# Tiny_PowerSpy.net
KiCad netlist of a schematic drawn in EAGLE
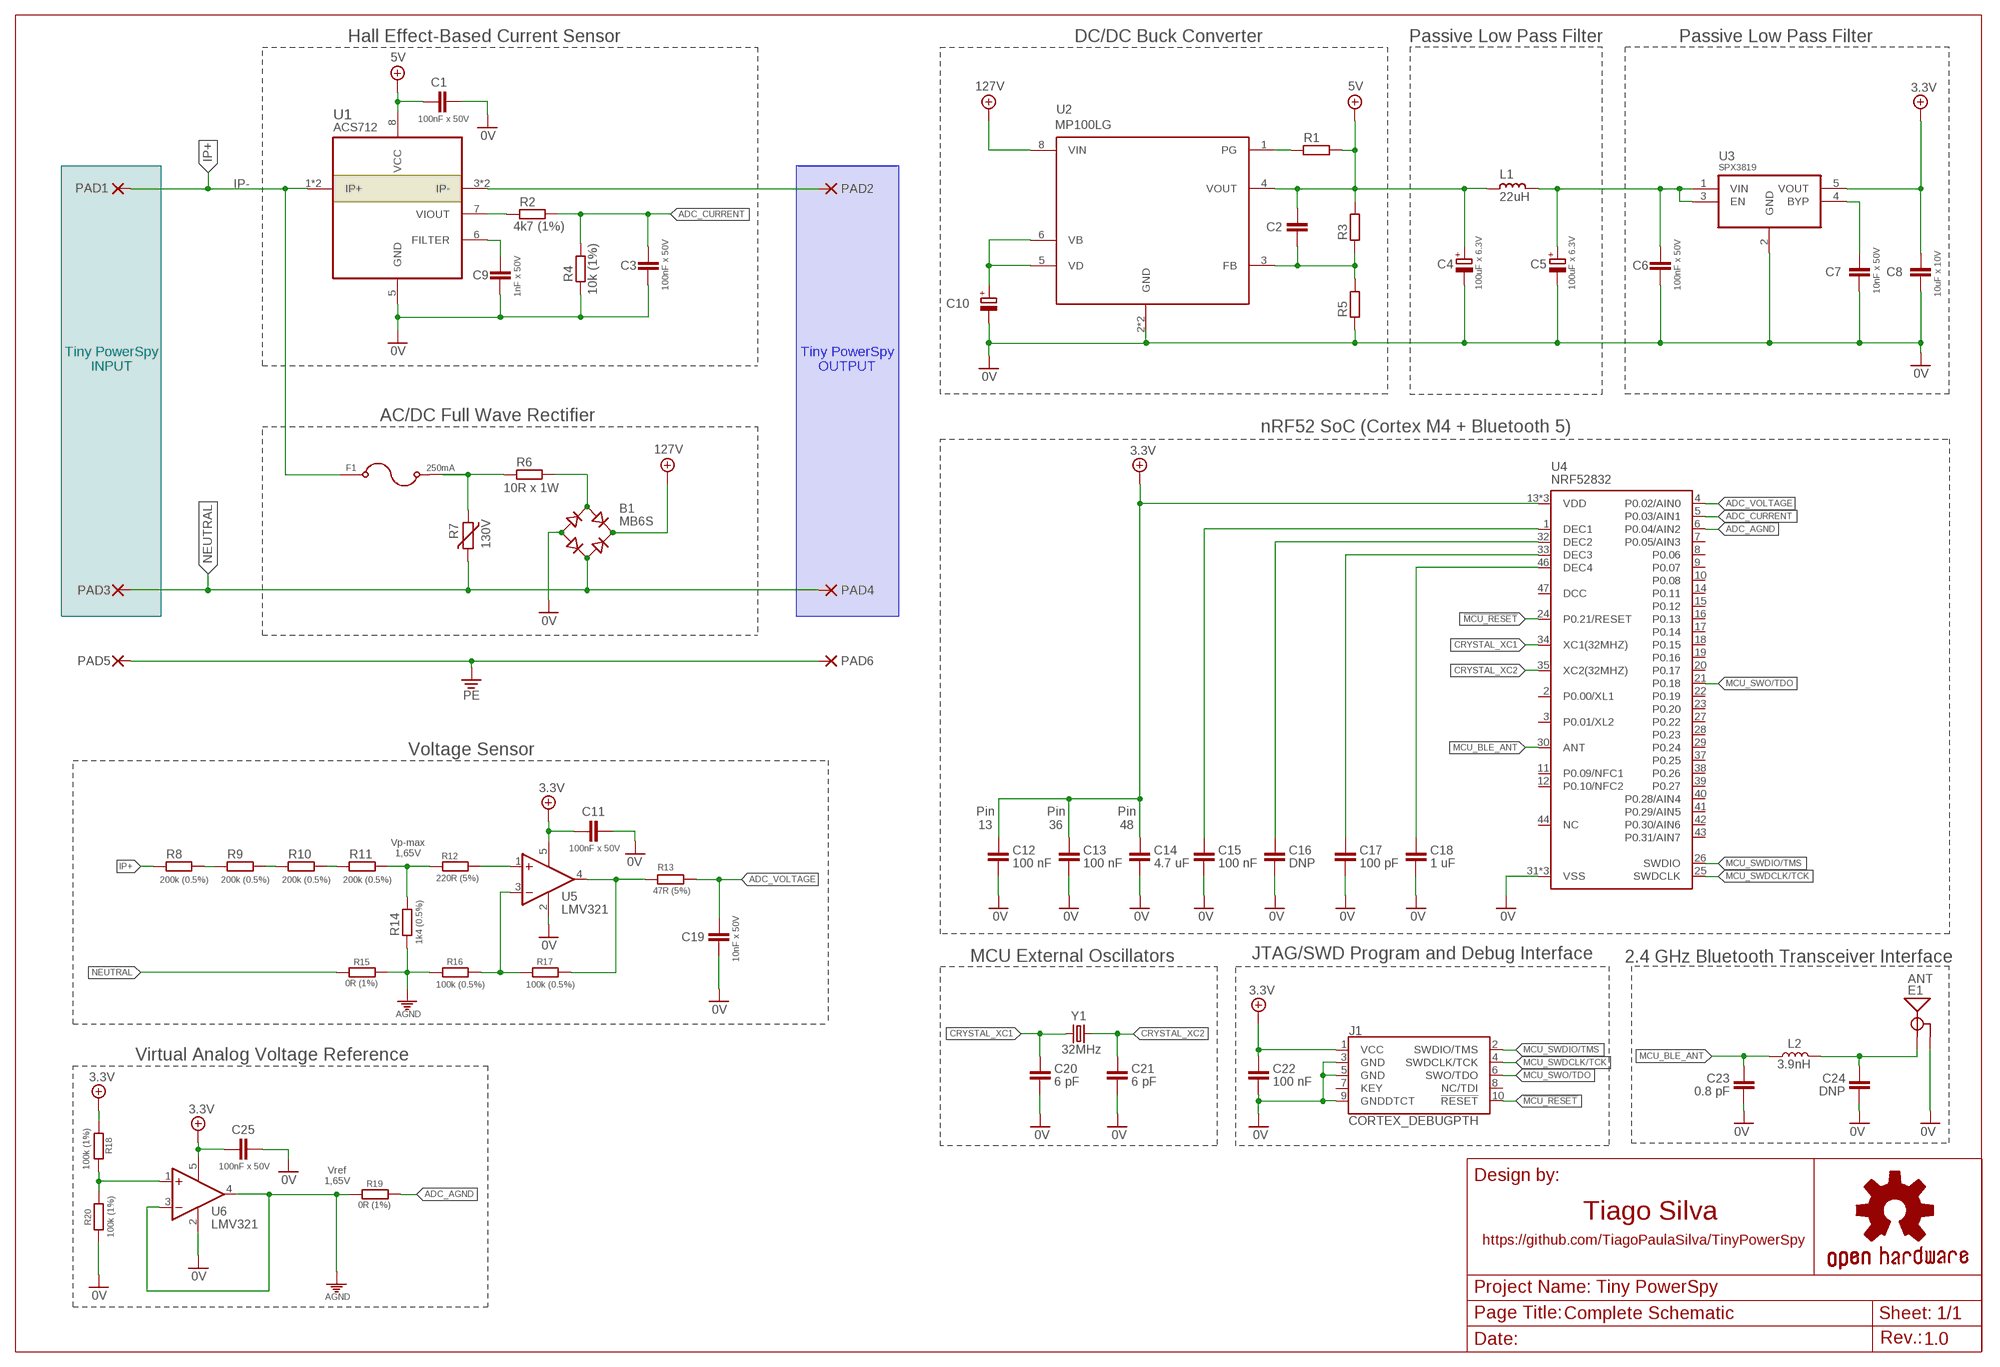
[diagram p0: schematic, sheet 1]

(export (version "E")
  (design (tool "Eeschema 10.0.6"))
  (components
    (comp (ref "B1")
      (value "MB6S")
      (footprint "eagle-import:SOIC-4")
      (libsource (lib "eagle-import") (part "MBS6"))
    )
    (comp (ref "C1")
      (value "100nF x 50V")
      (footprint "eagle-import:C0603")
      (libsource (lib "eagle-import") (part "C-EUC0603"))
    )
    (comp (ref "C2")
      (value "C-EUC0603")
      (footprint "eagle-import:C0603")
      (libsource (lib "eagle-import") (part "C-EUC0603"))
    )
    (comp (ref "C3")
      (value "100nF x 50V")
      (footprint "eagle-import:C0603")
      (libsource (lib "eagle-import") (part "C-EUC0603"))
    )
    (comp (ref "C4")
      (value "100uF x 6.3V")
      (footprint "eagle-import:C1206K")
      (libsource (lib "eagle-import") (part "C-USC1206K"))
    )
    (comp (ref "C5")
      (value "100uF x 6.3V")
      (footprint "eagle-import:C1206K")
      (libsource (lib "eagle-import") (part "C-USC1206K"))
    )
    (comp (ref "C6")
      (value "100nF x 50V")
      (footprint "eagle-import:C0603")
      (libsource (lib "eagle-import") (part "C-EUC0603"))
    )
    (comp (ref "C7")
      (value "10nF x 50V")
      (footprint "eagle-import:C0603")
      (libsource (lib "eagle-import") (part "C-EUC0603"))
    )
    (comp (ref "C8")
      (value "10uF x 10V")
      (footprint "eagle-import:C0603")
      (libsource (lib "eagle-import") (part "C-EUC0603"))
    )
    (comp (ref "C9")
      (value "1nF x 50V")
      (footprint "eagle-import:C0603")
      (libsource (lib "eagle-import") (part "C-EUC0603"))
    )
    (comp (ref "C10")
      (value "CPOL-EUE3.5-8")
      (footprint "eagle-import:E3,5-8")
      (libsource (lib "eagle-import") (part "CPOL-EUE3.5-8"))
    )
    (comp (ref "C11")
      (value "100nF x 50V")
      (footprint "eagle-import:C0603")
      (libsource (lib "eagle-import") (part "C-EUC0603"))
    )
    (comp (ref "C12")
      (value "100 nF")
      (footprint "eagle-import:C0402")
      (libsource (lib "eagle-import") (part "C-EUC0402"))
    )
    (comp (ref "C13")
      (value "100 nF")
      (footprint "eagle-import:C0402")
      (libsource (lib "eagle-import") (part "C-EUC0402"))
    )
    (comp (ref "C14")
      (value "4.7 uF")
      (footprint "eagle-import:C0603")
      (libsource (lib "eagle-import") (part "C-EUC0603"))
    )
    (comp (ref "C15")
      (value "100 nF")
      (footprint "eagle-import:C0402")
      (libsource (lib "eagle-import") (part "C-EUC0402"))
    )
    (comp (ref "C16")
      (value "DNP")
      (footprint "eagle-import:C0402")
      (libsource (lib "eagle-import") (part "C-EUC0402"))
    )
    (comp (ref "C17")
      (value "100 pF")
      (footprint "eagle-import:C0402")
      (libsource (lib "eagle-import") (part "C-EUC0402"))
    )
    (comp (ref "C18")
      (value "1 uF")
      (footprint "eagle-import:C0603")
      (libsource (lib "eagle-import") (part "C-EUC0603"))
    )
    (comp (ref "C19")
      (value "10nF x 50V")
      (footprint "eagle-import:C0603")
      (libsource (lib "eagle-import") (part "C-EUC0603"))
    )
    (comp (ref "C20")
      (value "6 pF")
      (footprint "eagle-import:C0402")
      (libsource (lib "eagle-import") (part "C-EUC0402"))
    )
    (comp (ref "C21")
      (value "6 pF")
      (footprint "eagle-import:C0402")
      (libsource (lib "eagle-import") (part "C-EUC0402"))
    )
    (comp (ref "C22")
      (value "100 nF")
      (footprint "eagle-import:C0603")
      (libsource (lib "eagle-import") (part "C-EUC0603"))
    )
    (comp (ref "C23")
      (value "0.8 pF")
      (footprint "eagle-import:C0603")
      (libsource (lib "eagle-import") (part "C-EUC0603"))
    )
    (comp (ref "C24")
      (value "DNP")
      (footprint "eagle-import:C0603")
      (libsource (lib "eagle-import") (part "C-EUC0603"))
    )
    (comp (ref "C25")
      (value "100nF x 50V")
      (footprint "eagle-import:C0603")
      (libsource (lib "eagle-import") (part "C-EUC0603"))
    )
    (comp (ref "E1")
      (value "ANT")
      (footprint "eagle-import:TRACE_ANTENNA_2.4GHZ_15.2MM")
      (libsource (lib "eagle-import") (part "ANTENNA-GROUNDEDTRACE-15.2MM"))
    )
    (comp (ref "F1")
      (value "250mA")
      (footprint "eagle-import:FUSE_0154004.DR")
      (fields
        (field (name "DIGI-KEY_PART_NUMBER") "F1227CT-ND")
        (field (name "MF") "Littelfuse Inc.")
        (field (name "MP") "0154004.DR")
      )
      (libsource (lib "eagle-import") (part "0154004.DR"))
    )
    (comp (ref "J1")
      (value "CORTEX_DEBUGPTH")
      (footprint "eagle-import:2X5-PTH-1.27MM")
      (libsource (lib "eagle-import") (part "CORTEX_DEBUGPTH"))
    )
    (comp (ref "L1")
      (value "22uH")
      (footprint "eagle-import:L0603")
      (libsource (lib "eagle-import") (part "L_0603"))
    )
    (comp (ref "L2")
      (value "3.9nH")
      (footprint "eagle-import:0402")
      (libsource (lib "eagle-import") (part "INDUCTOR-0402-3.9NH"))
    )
    (comp (ref "PAD1")
      (value "SMD5")
      (footprint "eagle-import:SMD2,54-5,08")
      (libsource (lib "eagle-import") (part "SMD5"))
    )
    (comp (ref "PAD2")
      (value "SMD5")
      (footprint "eagle-import:SMD2,54-5,08")
      (libsource (lib "eagle-import") (part "SMD5"))
    )
    (comp (ref "PAD3")
      (value "SMD2")
      (footprint "eagle-import:SMD1,27-2,54")
      (libsource (lib "eagle-import") (part "SMD2"))
    )
    (comp (ref "PAD4")
      (value "SMD5")
      (footprint "eagle-import:SMD2,54-5,08")
      (libsource (lib "eagle-import") (part "SMD5"))
    )
    (comp (ref "PAD5")
      (value "SMD2")
      (footprint "eagle-import:SMD1,27-2,54")
      (libsource (lib "eagle-import") (part "SMD2"))
    )
    (comp (ref "PAD6")
      (value "SMD5")
      (footprint "eagle-import:SMD2,54-5,08")
      (libsource (lib "eagle-import") (part "SMD5"))
    )
    (comp (ref "R1")
      (value "R-EU_R0603")
      (footprint "eagle-import:R0603")
      (libsource (lib "eagle-import") (part "R-EU_R0603"))
    )
    (comp (ref "R2")
      (value "4k7 (1%)")
      (footprint "eagle-import:R0603")
      (libsource (lib "eagle-import") (part "R-EU_R0603"))
    )
    (comp (ref "R3")
      (value "R-EU_R0603")
      (footprint "eagle-import:R0603")
      (libsource (lib "eagle-import") (part "R-EU_R0603"))
    )
    (comp (ref "R4")
      (value "10k (1%)")
      (footprint "eagle-import:R0603")
      (libsource (lib "eagle-import") (part "R-EU_R0603"))
    )
    (comp (ref "R5")
      (value "R-EU_R0603")
      (footprint "eagle-import:R0603")
      (libsource (lib "eagle-import") (part "R-EU_R0603"))
    )
    (comp (ref "R6")
      (value "10R x 1W")
      (footprint "eagle-import:0207_5V")
      (libsource (lib "eagle-import") (part "resistor pot_R-EU_0207/5V"))
    )
    (comp (ref "R7")
      (value "130V")
      (footprint "eagle-import:S05K11")
      (libsource (lib "eagle-import") (part "VARISTOR"))
    )
    (comp (ref "R8")
      (value "200k (0.5%)")
      (footprint "eagle-import:R0603")
      (libsource (lib "eagle-import") (part "R-EU_R0603"))
    )
    (comp (ref "R9")
      (value "200k (0.5%)")
      (footprint "eagle-import:R0603")
      (libsource (lib "eagle-import") (part "R-EU_R0603"))
    )
    (comp (ref "R10")
      (value "200k (0.5%)")
      (footprint "eagle-import:R0603")
      (libsource (lib "eagle-import") (part "R-EU_R0603"))
    )
    (comp (ref "R11")
      (value "200k (0.5%)")
      (footprint "eagle-import:R0603")
      (libsource (lib "eagle-import") (part "R-EU_R0603"))
    )
    (comp (ref "R12")
      (value "220R (5%)")
      (footprint "eagle-import:R0603")
      (libsource (lib "eagle-import") (part "R-EU_R0603"))
    )
    (comp (ref "R13")
      (value "47R (5%)")
      (footprint "eagle-import:R0603")
      (libsource (lib "eagle-import") (part "R-EU_R0603"))
    )
    (comp (ref "R14")
      (value "1k4 (0.5%)")
      (footprint "eagle-import:R0603")
      (libsource (lib "eagle-import") (part "R-EU_R0603"))
    )
    (comp (ref "R15")
      (value "0R (1%)")
      (footprint "eagle-import:R0603")
      (libsource (lib "eagle-import") (part "R-EU_R0603"))
    )
    (comp (ref "R16")
      (value "100k (0.5%)")
      (footprint "eagle-import:R0603")
      (libsource (lib "eagle-import") (part "R-EU_R0603"))
    )
    (comp (ref "R17")
      (value "100k (0.5%)")
      (footprint "eagle-import:R0603")
      (libsource (lib "eagle-import") (part "R-EU_R0603"))
    )
    (comp (ref "R18")
      (value "100k (1%)")
      (footprint "eagle-import:R0603")
      (libsource (lib "eagle-import") (part "R-EU_R0603"))
    )
    (comp (ref "R19")
      (value "0R (1%)")
      (footprint "eagle-import:R0603")
      (libsource (lib "eagle-import") (part "R-EU_R0603"))
    )
    (comp (ref "R20")
      (value "100k (1%)")
      (footprint "eagle-import:R0603")
      (libsource (lib "eagle-import") (part "R-EU_R0603"))
    )
    (comp (ref "U1")
      (value "ACS712")
      (footprint "eagle-import:SOIC127P600X175-8N")
      (fields (field (name "MF") "Allegro") (field (name "MP") "ACS712ELCTR-20A-T"))
      (libsource (lib "eagle-import") (part "ACS712ELCTR-20A-T"))
    )
    (comp (ref "U2")
      (value "MP100LG")
      (footprint "eagle-import:SOIC8E")
      (libsource (lib "eagle-import") (part "MP100LG"))
    )
    (comp (ref "U3")
      (value "SPX3819")
      (footprint "eagle-import:SOT95P280X145-5N")
      (fields (field (name "MF") "MaxLinear, Inc.") (field (name "MP") "SPX3819M5-L-3-3"))
      (libsource (lib "eagle-import") (part "SPX3819M5-L-3-3"))
    )
    (comp (ref "U4")
      (value "NRF52832")
      (footprint "eagle-import:QFN48-6X6MM")
      (libsource (lib "eagle-import") (part "NRF52832"))
    )
    (comp (ref "U5")
      (value "LMV321")
      (footprint "eagle-import:SOT23-5")
      (libsource (lib "eagle-import") (part "LMV321?M5"))
    )
    (comp (ref "U6")
      (value "LMV321")
      (footprint "eagle-import:SOT23-5")
      (libsource (lib "eagle-import") (part "LMV321?M5"))
    )
    (comp (ref "Y1")
      (value "32MHz")
      (footprint "eagle-import:CRYSTAL-SMD-2.0X1.6MM")
      (libsource (lib "eagle-import") (part "CRYSTAL-32MHZ-SMD-2.0X1.6MM"))
    )
  )
  (nets
    (net (code "1") (name "/IP-") (class "Default")
      (node (ref "PAD2") (pin "1") (pinfunction "P_1") (pintype "passive"))
      (node (ref "U1") (pin "3") (pinfunction "IP-_3") (pintype "input"))
      (node (ref "U1") (pin "4") (pinfunction "IP-_4") (pintype "input"))
    )
    (net (code "2") (name "/~{MCU_RESET}") (class "Default")
      (node (ref "J1") (pin "10") (pinfunction "~{RESET}_10") (pintype "bidirectional"))
      (node (ref "U4") (pin "24") (pinfunction "P0.21/RESET_24") (pintype "bidirectional"))
    )
    (net (code "3") (name "0V") (class "Default")
      (node (ref "B1") (pin "-") (pinfunction "-_-") (pintype "passive"))
      (node (ref "C1") (pin "1") (pinfunction "1_1") (pintype "passive"))
      (node (ref "C10") (pin "-") (pinfunction "-_-") (pintype "passive"))
      (node (ref "C11") (pin "1") (pinfunction "1_1") (pintype "passive"))
      (node (ref "C12") (pin "2") (pinfunction "2_2") (pintype "passive"))
      (node (ref "C13") (pin "2") (pinfunction "2_2") (pintype "passive"))
      (node (ref "C14") (pin "2") (pinfunction "2_2") (pintype "passive"))
      (node (ref "C15") (pin "2") (pinfunction "2_2") (pintype "passive"))
      (node (ref "C16") (pin "2") (pinfunction "2_2") (pintype "passive"))
      (node (ref "C17") (pin "2") (pinfunction "2_2") (pintype "passive"))
      (node (ref "C18") (pin "2") (pinfunction "2_2") (pintype "passive"))
      (node (ref "C19") (pin "2") (pinfunction "2_2") (pintype "passive"))
      (node (ref "C20") (pin "2") (pinfunction "2_2") (pintype "passive"))
      (node (ref "C21") (pin "2") (pinfunction "2_2") (pintype "passive"))
      (node (ref "C22") (pin "2") (pinfunction "2_2") (pintype "passive"))
      (node (ref "C23") (pin "2") (pinfunction "2_2") (pintype "passive"))
      (node (ref "C24") (pin "2") (pinfunction "2_2") (pintype "passive"))
      (node (ref "C25") (pin "2") (pinfunction "2_2") (pintype "passive"))
      (node (ref "C3") (pin "2") (pinfunction "2_2") (pintype "passive"))
      (node (ref "C4") (pin "2") (pinfunction "2_2") (pintype "passive"))
      (node (ref "C5") (pin "2") (pinfunction "2_2") (pintype "passive"))
      (node (ref "C6") (pin "2") (pinfunction "2_2") (pintype "passive"))
      (node (ref "C7") (pin "2") (pinfunction "2_2") (pintype "passive"))
      (node (ref "C8") (pin "2") (pinfunction "2_2") (pintype "passive"))
      (node (ref "C9") (pin "2") (pinfunction "2_2") (pintype "passive"))
      (node (ref "E1") (pin "GND") (pinfunction "GND_GND") (pintype "bidirectional"))
      (node (ref "J1") (pin "3") (pinfunction "GND_3") (pintype "bidirectional"))
      (node (ref "J1") (pin "5") (pinfunction "GND_5") (pintype "bidirectional"))
      (node (ref "J1") (pin "9") (pinfunction "GNDDTCT_9") (pintype "bidirectional"))
      (node (ref "R20") (pin "2") (pinfunction "2_2") (pintype "passive"))
      (node (ref "R4") (pin "2") (pinfunction "2_2") (pintype "passive"))
      (node (ref "R5") (pin "1") (pinfunction "1_1") (pintype "passive"))
      (node (ref "U1") (pin "5") (pinfunction "GND_5") (pintype "power_in"))
      (node (ref "U2") (pin "2") (pinfunction "GND_2") (pintype "bidirectional"))
      (node (ref "U2") (pin "9") (pinfunction "GND_9") (pintype "bidirectional"))
      (node (ref "U3") (pin "2") (pinfunction "GND_2") (pintype "passive"))
      (node (ref "U4") (pin "31") (pinfunction "VSS_31") (pintype "bidirectional"))
      (node (ref "U4") (pin "45") (pinfunction "VSS_45") (pintype "bidirectional"))
      (node (ref "U4") (pin "EP") (pinfunction "VSS_EP") (pintype "bidirectional"))
      (node (ref "U5") (pin "2") (pinfunction "V-_2") (pintype "power_in"))
      (node (ref "U6") (pin "2") (pinfunction "V-_2") (pintype "power_in"))
    )
    (net (code "4") (name "3.3V") (class "Default")
      (node (ref "C11") (pin "2") (pinfunction "2_2") (pintype "passive"))
      (node (ref "C12") (pin "1") (pinfunction "1_1") (pintype "passive"))
      (node (ref "C13") (pin "1") (pinfunction "1_1") (pintype "passive"))
      (node (ref "C14") (pin "1") (pinfunction "1_1") (pintype "passive"))
      (node (ref "C22") (pin "1") (pinfunction "1_1") (pintype "passive"))
      (node (ref "C25") (pin "1") (pinfunction "1_1") (pintype "passive"))
      (node (ref "C8") (pin "1") (pinfunction "1_1") (pintype "passive"))
      (node (ref "J1") (pin "1") (pinfunction "VCC_1") (pintype "bidirectional"))
      (node (ref "R18") (pin "2") (pinfunction "2_2") (pintype "passive"))
      (node (ref "U3") (pin "5") (pinfunction "VOUT_5") (pintype "output"))
      (node (ref "U4") (pin "13") (pinfunction "VDD_13") (pintype "bidirectional"))
      (node (ref "U4") (pin "36") (pinfunction "VDD_36") (pintype "bidirectional"))
      (node (ref "U4") (pin "48") (pinfunction "VDD_48") (pintype "bidirectional"))
      (node (ref "U5") (pin "5") (pinfunction "V+_5") (pintype "power_in"))
      (node (ref "U6") (pin "5") (pinfunction "V+_5") (pintype "power_in"))
    )
    (net (code "5") (name "5V") (class "Default")
      (node (ref "C1") (pin "2") (pinfunction "2_2") (pintype "passive"))
      (node (ref "C2") (pin "1") (pinfunction "1_1") (pintype "passive"))
      (node (ref "C4") (pin "1") (pinfunction "1_1") (pintype "passive"))
      (node (ref "L1") (pin "2") (pinfunction "2_2") (pintype "passive"))
      (node (ref "R1") (pin "2") (pinfunction "2_2") (pintype "passive"))
      (node (ref "R3") (pin "2") (pinfunction "2_2") (pintype "passive"))
      (node (ref "U1") (pin "8") (pinfunction "VCC_8") (pintype "power_in"))
      (node (ref "U2") (pin "4") (pinfunction "VOUT_4") (pintype "bidirectional"))
    )
    (net (code "6") (name "127V") (class "Default")
      (node (ref "B1") (pin "+") (pinfunction "+_+") (pintype "passive"))
      (node (ref "U2") (pin "8") (pinfunction "VIN_8") (pintype "bidirectional"))
    )
    (net (code "7") (name "ADC_AGND") (class "Default")
      (node (ref "R19") (pin "2") (pinfunction "2_2") (pintype "passive"))
      (node (ref "U4") (pin "6") (pinfunction "P0.04/AIN2_6") (pintype "bidirectional"))
    )
    (net (code "8") (name "ADC_CURRENT") (class "Default")
      (node (ref "C3") (pin "1") (pinfunction "1_1") (pintype "passive"))
      (node (ref "R2") (pin "2") (pinfunction "2_2") (pintype "passive"))
      (node (ref "R4") (pin "1") (pinfunction "1_1") (pintype "passive"))
      (node (ref "U4") (pin "5") (pinfunction "P0.03/AIN1_5") (pintype "bidirectional"))
    )
    (net (code "9") (name "ADC_VOLTAGE") (class "Default")
      (node (ref "C19") (pin "1") (pinfunction "1_1") (pintype "passive"))
      (node (ref "R13") (pin "1") (pinfunction "1_1") (pintype "passive"))
      (node (ref "U4") (pin "4") (pinfunction "P0.02/AIN0_4") (pintype "bidirectional"))
    )
    (net (code "10") (name "AGND") (class "Default")
      (node (ref "R14") (pin "2") (pinfunction "2_2") (pintype "passive"))
      (node (ref "R15") (pin "2") (pinfunction "2_2") (pintype "passive"))
      (node (ref "R16") (pin "2") (pinfunction "2_2") (pintype "passive"))
      (node (ref "R19") (pin "1") (pinfunction "1_1") (pintype "passive"))
      (node (ref "U6") (pin "3") (pinfunction "-IN_3") (pintype "input"))
      (node (ref "U6") (pin "4") (pinfunction "OUT_4") (pintype "output"))
    )
    (net (code "11") (name "CRYSTAL_XC1") (class "Default")
      (node (ref "C20") (pin "1") (pinfunction "1_1") (pintype "passive"))
      (node (ref "U4") (pin "34") (pinfunction "XC1(32MHZ)_34") (pintype "bidirectional"))
      (node (ref "Y1") (pin "3") (pinfunction "2_3") (pintype "passive"))
    )
    (net (code "12") (name "CRYSTAL_XC2") (class "Default")
      (node (ref "C21") (pin "1") (pinfunction "1_1") (pintype "passive"))
      (node (ref "U4") (pin "35") (pinfunction "XC2(32MHZ)_35") (pintype "bidirectional"))
      (node (ref "Y1") (pin "1") (pinfunction "1_1") (pintype "passive"))
    )
    (net (code "13") (name "IP+") (class "Default")
      (node (ref "F1") (pin "1") (pinfunction "1_1") (pintype "passive"))
      (node (ref "PAD1") (pin "1") (pinfunction "P_1") (pintype "passive"))
      (node (ref "R8") (pin "1") (pinfunction "1_1") (pintype "passive"))
      (node (ref "U1") (pin "1") (pinfunction "IP+_1") (pintype "input"))
      (node (ref "U1") (pin "2") (pinfunction "IP+_2") (pintype "input"))
    )
    (net (code "14") (name "MCU_BLE_ANT") (class "Default")
      (node (ref "C23") (pin "1") (pinfunction "1_1") (pintype "passive"))
      (node (ref "L2") (pin "2") (pinfunction "2_2") (pintype "passive"))
      (node (ref "U4") (pin "30") (pinfunction "ANT_30") (pintype "bidirectional"))
    )
    (net (code "15") (name "MCU_SWDCLK{slash}TCK") (class "Default")
      (node (ref "J1") (pin "4") (pinfunction "SWDCLK/TCK_4") (pintype "bidirectional"))
      (node (ref "U4") (pin "25") (pinfunction "SWDCLK_25") (pintype "bidirectional"))
    )
    (net (code "16") (name "MCU_SWDIO{slash}TMS") (class "Default")
      (node (ref "J1") (pin "2") (pinfunction "SWDIO/TMS_2") (pintype "bidirectional"))
      (node (ref "U4") (pin "26") (pinfunction "SWDIO_26") (pintype "bidirectional"))
    )
    (net (code "17") (name "MCU_SWO{slash}TDO") (class "Default")
      (node (ref "J1") (pin "6") (pinfunction "SWO/TDO_6") (pintype "bidirectional"))
      (node (ref "U4") (pin "21") (pinfunction "P0.18_21") (pintype "bidirectional"))
    )
    (net (code "18") (name "NEUTRAL") (class "Default")
      (node (ref "B1") (pin "~2") (pinfunction "AC2_~2") (pintype "passive"))
      (node (ref "PAD3") (pin "1") (pinfunction "P_1") (pintype "passive"))
      (node (ref "PAD4") (pin "1") (pinfunction "P_1") (pintype "passive"))
      (node (ref "R15") (pin "1") (pinfunction "1_1") (pintype "passive"))
      (node (ref "R7") (pin "2") (pinfunction "2_2") (pintype "passive"))
    )
    (net (code "19") (name "Net-(B1-AC1)") (class "Default")
      (node (ref "B1") (pin "~1") (pinfunction "AC1_~1") (pintype "passive"))
      (node (ref "R6") (pin "2") (pinfunction "2_2") (pintype "passive"))
    )
    (net (code "20") (name "Net-(E1-SIGNAL)") (class "Default")
      (node (ref "C24") (pin "1") (pinfunction "1_1") (pintype "passive"))
      (node (ref "E1") (pin "ANT") (pinfunction "SIGNAL_ANT") (pintype "bidirectional"))
      (node (ref "L2") (pin "1") (pinfunction "1_1") (pintype "passive"))
    )
    (net (code "21") (name "Net-(F1-Pad2)") (class "Default")
      (node (ref "F1") (pin "2") (pinfunction "2_2") (pintype "passive"))
      (node (ref "R6") (pin "1") (pinfunction "1_1") (pintype "passive"))
      (node (ref "R7") (pin "1") (pinfunction "1_1") (pintype "passive"))
    )
    (net (code "22") (name "Net-(R8-Pad2)") (class "Default")
      (node (ref "R8") (pin "2") (pinfunction "2_2") (pintype "passive"))
      (node (ref "R9") (pin "1") (pinfunction "1_1") (pintype "passive"))
    )
    (net (code "23") (name "Net-(R10-Pad1)") (class "Default")
      (node (ref "R10") (pin "1") (pinfunction "1_1") (pintype "passive"))
      (node (ref "R9") (pin "2") (pinfunction "2_2") (pintype "passive"))
    )
    (net (code "24") (name "Net-(R10-Pad2)") (class "Default")
      (node (ref "R10") (pin "2") (pinfunction "2_2") (pintype "passive"))
      (node (ref "R11") (pin "1") (pinfunction "1_1") (pintype "passive"))
    )
    (net (code "25") (name "Net-(R11-Pad2)") (class "Default")
      (node (ref "R11") (pin "2") (pinfunction "2_2") (pintype "passive"))
      (node (ref "R12") (pin "2") (pinfunction "2_2") (pintype "passive"))
      (node (ref "R14") (pin "1") (pinfunction "1_1") (pintype "passive"))
    )
    (net (code "26") (name "Net-(U1-FILTER)") (class "Default")
      (node (ref "C9") (pin "1") (pinfunction "1_1") (pintype "passive"))
      (node (ref "U1") (pin "6") (pinfunction "FILTER_6") (pintype "input"))
    )
    (net (code "27") (name "Net-(U1-VIOUT)") (class "Default")
      (node (ref "R2") (pin "1") (pinfunction "1_1") (pintype "passive"))
      (node (ref "U1") (pin "7") (pinfunction "VIOUT_7") (pintype "output"))
    )
    (net (code "28") (name "Net-(U2-FB)") (class "Default")
      (node (ref "C2") (pin "2") (pinfunction "2_2") (pintype "passive"))
      (node (ref "R3") (pin "1") (pinfunction "1_1") (pintype "passive"))
      (node (ref "R5") (pin "2") (pinfunction "2_2") (pintype "passive"))
      (node (ref "U2") (pin "3") (pinfunction "FB_3") (pintype "bidirectional"))
    )
    (net (code "29") (name "Net-(U2-PG)") (class "Default")
      (node (ref "R1") (pin "1") (pinfunction "1_1") (pintype "passive"))
      (node (ref "U2") (pin "1") (pinfunction "PG_1") (pintype "bidirectional"))
    )
    (net (code "30") (name "Net-(U2-VB)") (class "Default")
      (node (ref "C10") (pin "+") (pinfunction "+_+") (pintype "passive"))
      (node (ref "U2") (pin "5") (pinfunction "VD_5") (pintype "bidirectional"))
      (node (ref "U2") (pin "6") (pinfunction "VB_6") (pintype "bidirectional"))
    )
    (net (code "31") (name "Net-(U3-BYP)") (class "Default")
      (node (ref "C7") (pin "1") (pinfunction "1_1") (pintype "passive"))
      (node (ref "U3") (pin "4") (pinfunction "BYP_4") (pintype "passive"))
    )
    (net (code "32") (name "Net-(U3-EN)") (class "Default")
      (node (ref "C5") (pin "1") (pinfunction "1_1") (pintype "passive"))
      (node (ref "C6") (pin "1") (pinfunction "1_1") (pintype "passive"))
      (node (ref "L1") (pin "1") (pinfunction "1_1") (pintype "passive"))
      (node (ref "U3") (pin "1") (pinfunction "VIN_1") (pintype "power_in"))
      (node (ref "U3") (pin "3") (pinfunction "EN_3") (pintype "input"))
    )
    (net (code "33") (name "Net-(U4-DEC1)") (class "Default")
      (node (ref "C15") (pin "1") (pinfunction "1_1") (pintype "passive"))
      (node (ref "U4") (pin "1") (pinfunction "DEC1_1") (pintype "bidirectional"))
    )
    (net (code "34") (name "Net-(U4-DEC2)") (class "Default")
      (node (ref "C16") (pin "1") (pinfunction "1_1") (pintype "passive"))
      (node (ref "U4") (pin "32") (pinfunction "DEC2_32") (pintype "bidirectional"))
    )
    (net (code "35") (name "Net-(U4-DEC3)") (class "Default")
      (node (ref "C17") (pin "1") (pinfunction "1_1") (pintype "passive"))
      (node (ref "U4") (pin "33") (pinfunction "DEC3_33") (pintype "bidirectional"))
    )
    (net (code "36") (name "Net-(U4-DEC4)") (class "Default")
      (node (ref "C18") (pin "1") (pinfunction "1_1") (pintype "passive"))
      (node (ref "U4") (pin "46") (pinfunction "DEC4_46") (pintype "bidirectional"))
    )
    (net (code "37") (name "Net-(U5-+IN)") (class "Default")
      (node (ref "R12") (pin "1") (pinfunction "1_1") (pintype "passive"))
      (node (ref "U5") (pin "1") (pinfunction "+IN_1") (pintype "input"))
    )
    (net (code "38") (name "Net-(U5--IN)") (class "Default")
      (node (ref "R16") (pin "1") (pinfunction "1_1") (pintype "passive"))
      (node (ref "R17") (pin "2") (pinfunction "2_2") (pintype "passive"))
      (node (ref "U5") (pin "3") (pinfunction "-IN_3") (pintype "input"))
    )
    (net (code "39") (name "Net-(U5-OUT)") (class "Default")
      (node (ref "R13") (pin "2") (pinfunction "2_2") (pintype "passive"))
      (node (ref "R17") (pin "1") (pinfunction "1_1") (pintype "passive"))
      (node (ref "U5") (pin "4") (pinfunction "OUT_4") (pintype "output"))
    )
    (net (code "40") (name "Net-(U6-+IN)") (class "Default")
      (node (ref "R18") (pin "1") (pinfunction "1_1") (pintype "passive"))
      (node (ref "R20") (pin "1") (pinfunction "1_1") (pintype "passive"))
      (node (ref "U6") (pin "1") (pinfunction "+IN_1") (pintype "input"))
    )
    (net (code "41") (name "PE") (class "Default")
      (node (ref "PAD5") (pin "1") (pinfunction "P_1") (pintype "passive"))
      (node (ref "PAD6") (pin "1") (pinfunction "P_1") (pintype "passive"))
    )
    (net (code "42") (name "unconnected-(J1-KEY-Pad7)") (class "Default")
      (node (ref "J1") (pin "7") (pinfunction "KEY_7") (pintype "bidirectional"))
    )
    (net (code "43") (name "unconnected-(J1-NC{slash}TDI-Pad8)") (class "Default")
      (node (ref "J1") (pin "8") (pinfunction "NC/TDI_8") (pintype "bidirectional"))
    )
    (net (code "44") (name "unconnected-(U4-DCC-Pad47)") (class "Default")
      (node (ref "U4") (pin "47") (pinfunction "DCC_47") (pintype "bidirectional"))
    )
    (net (code "45") (name "unconnected-(U4-NC-Pad44)") (class "Default")
      (node (ref "U4") (pin "44") (pinfunction "NC_44") (pintype "bidirectional"))
    )
    (net (code "46") (name "unconnected-(U4-P0.00{slash}XL1-Pad2)") (class "Default")
      (node (ref "U4") (pin "2") (pinfunction "P0.00/XL1_2") (pintype "bidirectional"))
    )
    (net (code "47") (name "unconnected-(U4-P0.01{slash}XL2-Pad3)") (class "Default")
      (node (ref "U4") (pin "3") (pinfunction "P0.01/XL2_3") (pintype "bidirectional"))
    )
    (net (code "48") (name "unconnected-(U4-P0.05{slash}AIN3-Pad7)") (class "Default")
      (node (ref "U4") (pin "7") (pinfunction "P0.05/AIN3_7") (pintype "bidirectional"))
    )
    (net (code "49") (name "unconnected-(U4-P0.06-Pad8)") (class "Default")
      (node (ref "U4") (pin "8") (pinfunction "P0.06_8") (pintype "bidirectional"))
    )
    (net (code "50") (name "unconnected-(U4-P0.07-Pad9)") (class "Default")
      (node (ref "U4") (pin "9") (pinfunction "P0.07_9") (pintype "bidirectional"))
    )
    (net (code "51") (name "unconnected-(U4-P0.08-Pad10)") (class "Default")
      (node (ref "U4") (pin "10") (pinfunction "P0.08_10") (pintype "bidirectional"))
    )
    (net (code "52") (name "unconnected-(U4-P0.09{slash}NFC1-Pad11)") (class "Default")
      (node (ref "U4") (pin "11") (pinfunction "P0.09/NFC1_11") (pintype "bidirectional"))
    )
    (net (code "53") (name "unconnected-(U4-P0.10{slash}NFC2-Pad12)") (class "Default")
      (node (ref "U4") (pin "12") (pinfunction "P0.10/NFC2_12") (pintype "bidirectional"))
    )
    (net (code "54") (name "unconnected-(U4-P0.11-Pad14)") (class "Default")
      (node (ref "U4") (pin "14") (pinfunction "P0.11_14") (pintype "bidirectional"))
    )
    (net (code "55") (name "unconnected-(U4-P0.12-Pad15)") (class "Default")
      (node (ref "U4") (pin "15") (pinfunction "P0.12_15") (pintype "bidirectional"))
    )
    (net (code "56") (name "unconnected-(U4-P0.13-Pad16)") (class "Default")
      (node (ref "U4") (pin "16") (pinfunction "P0.13_16") (pintype "bidirectional"))
    )
    (net (code "57") (name "unconnected-(U4-P0.14-Pad17)") (class "Default")
      (node (ref "U4") (pin "17") (pinfunction "P0.14_17") (pintype "bidirectional"))
    )
    (net (code "58") (name "unconnected-(U4-P0.15-Pad18)") (class "Default")
      (node (ref "U4") (pin "18") (pinfunction "P0.15_18") (pintype "bidirectional"))
    )
    (net (code "59") (name "unconnected-(U4-P0.16-Pad19)") (class "Default")
      (node (ref "U4") (pin "19") (pinfunction "P0.16_19") (pintype "bidirectional"))
    )
    (net (code "60") (name "unconnected-(U4-P0.17-Pad20)") (class "Default")
      (node (ref "U4") (pin "20") (pinfunction "P0.17_20") (pintype "bidirectional"))
    )
    (net (code "61") (name "unconnected-(U4-P0.19-Pad22)") (class "Default")
      (node (ref "U4") (pin "22") (pinfunction "P0.19_22") (pintype "bidirectional"))
    )
    (net (code "62") (name "unconnected-(U4-P0.20-Pad23)") (class "Default")
      (node (ref "U4") (pin "23") (pinfunction "P0.20_23") (pintype "bidirectional"))
    )
    (net (code "63") (name "unconnected-(U4-P0.22-Pad27)") (class "Default")
      (node (ref "U4") (pin "27") (pinfunction "P0.22_27") (pintype "bidirectional"))
    )
    (net (code "64") (name "unconnected-(U4-P0.23-Pad28)") (class "Default")
      (node (ref "U4") (pin "28") (pinfunction "P0.23_28") (pintype "bidirectional"))
    )
    (net (code "65") (name "unconnected-(U4-P0.24-Pad29)") (class "Default")
      (node (ref "U4") (pin "29") (pinfunction "P0.24_29") (pintype "bidirectional"))
    )
    (net (code "66") (name "unconnected-(U4-P0.25-Pad37)") (class "Default")
      (node (ref "U4") (pin "37") (pinfunction "P0.25_37") (pintype "bidirectional"))
    )
    (net (code "67") (name "unconnected-(U4-P0.26-Pad38)") (class "Default")
      (node (ref "U4") (pin "38") (pinfunction "P0.26_38") (pintype "bidirectional"))
    )
    (net (code "68") (name "unconnected-(U4-P0.27-Pad39)") (class "Default")
      (node (ref "U4") (pin "39") (pinfunction "P0.27_39") (pintype "bidirectional"))
    )
    (net (code "69") (name "unconnected-(U4-P0.28{slash}AIN4-Pad40)") (class "Default")
      (node (ref "U4") (pin "40") (pinfunction "P0.28/AIN4_40") (pintype "bidirectional"))
    )
    (net (code "70") (name "unconnected-(U4-P0.29{slash}AIN5-Pad41)") (class "Default")
      (node (ref "U4") (pin "41") (pinfunction "P0.29/AIN5_41") (pintype "bidirectional"))
    )
    (net (code "71") (name "unconnected-(U4-P0.30{slash}AIN6-Pad42)") (class "Default")
      (node (ref "U4") (pin "42") (pinfunction "P0.30/AIN6_42") (pintype "bidirectional"))
    )
    (net (code "72") (name "unconnected-(U4-P0.31{slash}AIN7-Pad43)") (class "Default")
      (node (ref "U4") (pin "43") (pinfunction "P0.31/AIN7_43") (pintype "bidirectional"))
    )
  )
)
